# LandPatternBreakouts.net
KiCad netlist of a schematic drawn in EAGLE
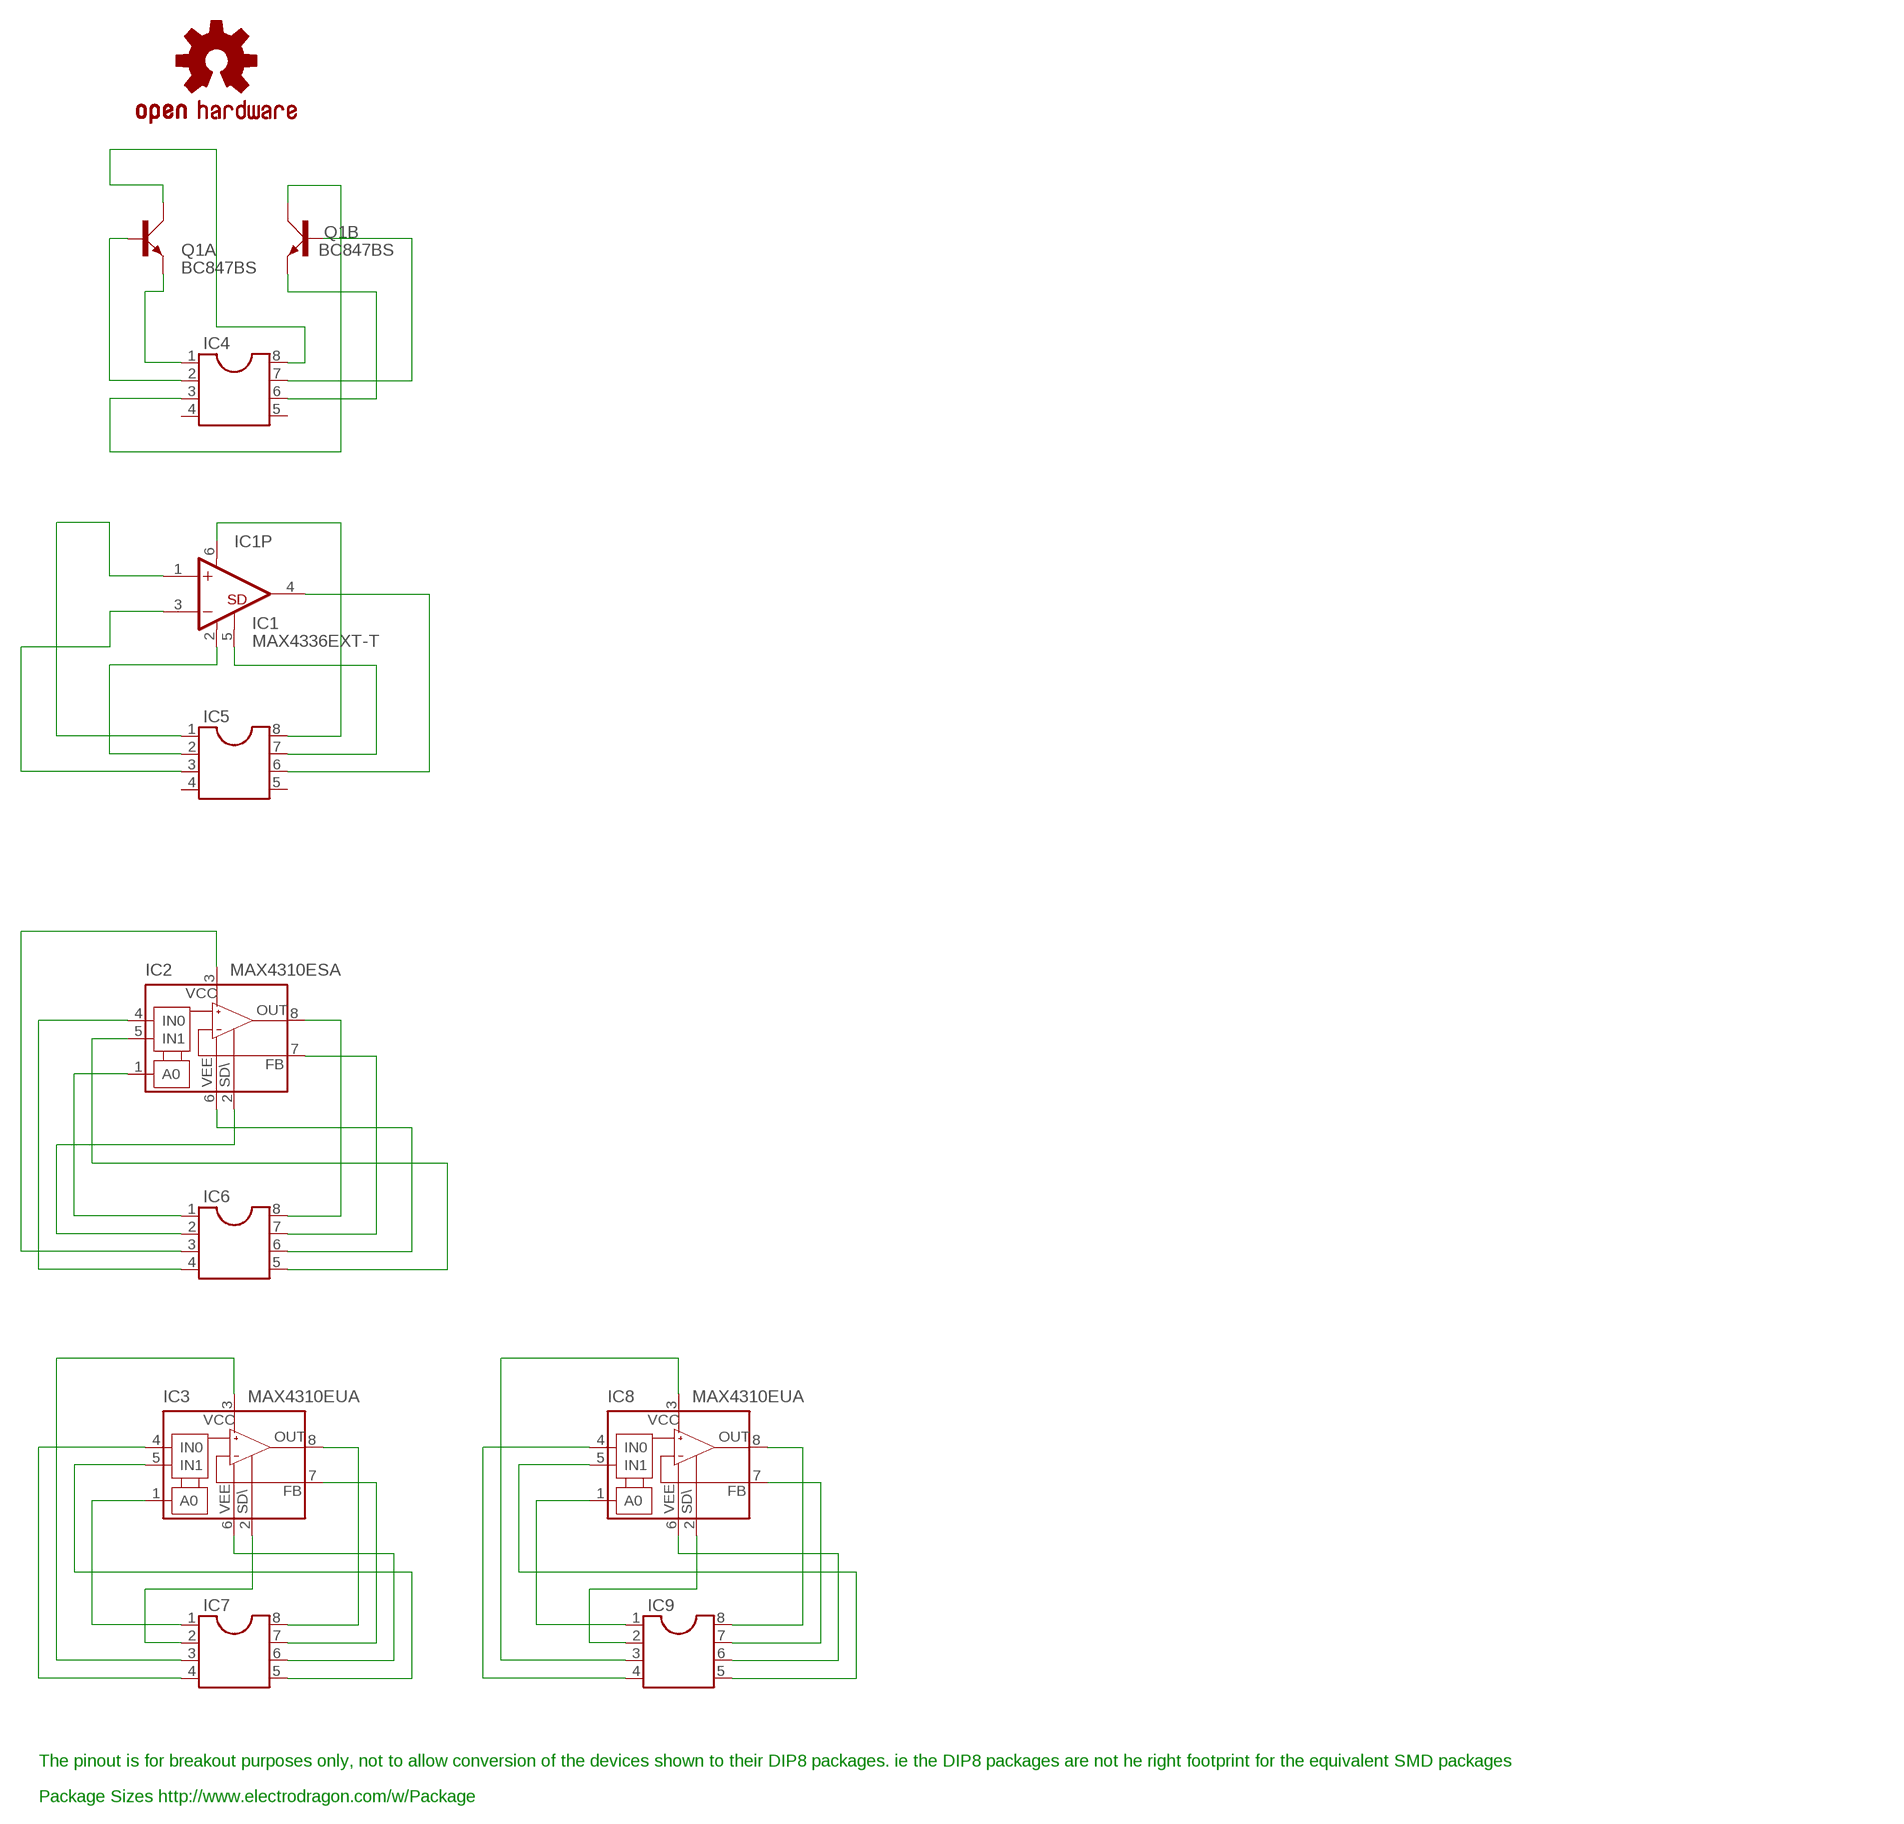
[diagram p0: schematic, sheet 1]

(export (version "E")
  (design (tool "Eeschema 10.0.6"))
  (components
    (comp (ref "IC1")
      (value "MAX4336EXT-T")
      (footprint "eagle-import:SOT23-6L")
      (fields (field (name "MPN") "MAX4336EXT+T"))
      (libsource (lib "eagle-import") (part "MAX4336EXT-T"))
    )
    (comp (ref "IC2")
      (value "MAX4310ESA")
      (footprint "eagle-import:UMAX8")
      (libsource (lib "eagle-import") (part "MAX4310ESA"))
    )
    (comp (ref "IC3")
      (value "MAX4310EUA")
      (footprint "eagle-import:SO08")
      (libsource (lib "eagle-import") (part "MAX4310EUA"))
    )
    (comp (ref "IC4")
      (value "DIL8")
      (footprint "eagle-import:DIL08")
      (libsource (lib "eagle-import") (part "DIL8"))
    )
    (comp (ref "IC5")
      (value "DIL8")
      (footprint "eagle-import:DIL08")
      (libsource (lib "eagle-import") (part "DIL8"))
    )
    (comp (ref "IC6")
      (value "DIL8")
      (footprint "eagle-import:DIL08")
      (libsource (lib "eagle-import") (part "DIL8"))
    )
    (comp (ref "IC7")
      (value "DIL8")
      (footprint "eagle-import:DIL08")
      (libsource (lib "eagle-import") (part "DIL8"))
    )
    (comp (ref "IC8")
      (value "MAX4310EUA")
      (footprint "eagle-import:SO08")
      (libsource (lib "eagle-import") (part "MAX4310EUA"))
    )
    (comp (ref "IC9")
      (value "DIL8")
      (footprint "eagle-import:DIL08")
      (libsource (lib "eagle-import") (part "DIL8"))
    )
    (comp (ref "LOGO1")
      (value "OSHW-LOGOS")
      (footprint "eagle-import:OSHW-LOGO-S")
      (libsource (lib "eagle-import") (part "OSHW-LOGOS"))
    )
    (comp (ref "Q1")
      (value "BC847BS")
      (footprint "eagle-import:SOT363_PHILIPS")
      (libsource (lib "eagle-import") (part "BC847BS"))
    )
  )
  (nets
    (net (code "1") (name "Net-(IC1A-+IN)") (class "Default")
      (node (ref "IC1") (pin "1") (pinfunction "+IN_1") (pintype "input"))
      (node (ref "IC5") (pin "1") (pinfunction "1_1") (pintype "passive"))
    )
    (net (code "2") (name "Net-(IC1A--IN)") (class "Default")
      (node (ref "IC1") (pin "3") (pinfunction "-IN_3") (pintype "input"))
      (node (ref "IC5") (pin "3") (pinfunction "3_3") (pintype "passive"))
    )
    (net (code "3") (name "Net-(IC1A-OUT)") (class "Default")
      (node (ref "IC1") (pin "4") (pinfunction "OUT_4") (pintype "output"))
      (node (ref "IC5") (pin "6") (pinfunction "6_6") (pintype "passive"))
    )
    (net (code "4") (name "Net-(IC1A-SHUTDOWN)") (class "Default")
      (node (ref "IC1") (pin "5") (pinfunction "SHUTDOWN_5") (pintype "passive"))
      (node (ref "IC5") (pin "7") (pinfunction "7_7") (pintype "passive"))
    )
    (net (code "5") (name "Net-(IC1B-V+)") (class "Default")
      (node (ref "IC1") (pin "6") (pinfunction "V+_6") (pintype "power_in"))
      (node (ref "IC5") (pin "8") (pinfunction "8_8") (pintype "passive"))
    )
    (net (code "6") (name "Net-(IC1B-V-)") (class "Default")
      (node (ref "IC1") (pin "2") (pinfunction "V-_2") (pintype "power_in"))
      (node (ref "IC5") (pin "2") (pinfunction "2_2") (pintype "passive"))
    )
    (net (code "7") (name "Net-(IC2-A0)") (class "Default")
      (node (ref "IC2") (pin "1") (pinfunction "A0_1") (pintype "input"))
      (node (ref "IC6") (pin "1") (pinfunction "1_1") (pintype "passive"))
    )
    (net (code "8") (name "Net-(IC2-FB)") (class "Default")
      (node (ref "IC2") (pin "7") (pinfunction "FB_7") (pintype "power_in"))
      (node (ref "IC6") (pin "7") (pinfunction "7_7") (pintype "passive"))
    )
    (net (code "9") (name "Net-(IC2-IN0)") (class "Default")
      (node (ref "IC2") (pin "4") (pinfunction "IN0_4") (pintype "input"))
      (node (ref "IC6") (pin "4") (pinfunction "4_4") (pintype "passive"))
    )
    (net (code "10") (name "Net-(IC2-IN1)") (class "Default")
      (node (ref "IC2") (pin "5") (pinfunction "IN1_5") (pintype "input"))
      (node (ref "IC6") (pin "5") (pinfunction "5_5") (pintype "passive"))
    )
    (net (code "11") (name "Net-(IC2-OUT)") (class "Default")
      (node (ref "IC2") (pin "8") (pinfunction "OUT_8") (pintype "output"))
      (node (ref "IC6") (pin "8") (pinfunction "8_8") (pintype "passive"))
    )
    (net (code "12") (name "Net-(IC2-V+)") (class "Default")
      (node (ref "IC2") (pin "3") (pinfunction "V+_3") (pintype "power_in"))
      (node (ref "IC6") (pin "3") (pinfunction "3_3") (pintype "passive"))
    )
    (net (code "13") (name "Net-(IC2-V-)") (class "Default")
      (node (ref "IC2") (pin "6") (pinfunction "V-_6") (pintype "power_in"))
      (node (ref "IC6") (pin "6") (pinfunction "6_6") (pintype "passive"))
    )
    (net (code "14") (name "Net-(IC2-~{SHDN})") (class "Default")
      (node (ref "IC2") (pin "2") (pinfunction "~{SHDN}_2") (pintype "input"))
      (node (ref "IC6") (pin "2") (pinfunction "2_2") (pintype "passive"))
    )
    (net (code "15") (name "Net-(IC3-A0)") (class "Default")
      (node (ref "IC3") (pin "1") (pinfunction "A0_1") (pintype "input"))
      (node (ref "IC7") (pin "1") (pinfunction "1_1") (pintype "passive"))
    )
    (net (code "16") (name "Net-(IC3-FB)") (class "Default")
      (node (ref "IC3") (pin "7") (pinfunction "FB_7") (pintype "power_in"))
      (node (ref "IC7") (pin "7") (pinfunction "7_7") (pintype "passive"))
    )
    (net (code "17") (name "Net-(IC3-IN0)") (class "Default")
      (node (ref "IC3") (pin "4") (pinfunction "IN0_4") (pintype "input"))
      (node (ref "IC7") (pin "4") (pinfunction "4_4") (pintype "passive"))
    )
    (net (code "18") (name "Net-(IC3-IN1)") (class "Default")
      (node (ref "IC3") (pin "5") (pinfunction "IN1_5") (pintype "input"))
      (node (ref "IC7") (pin "5") (pinfunction "5_5") (pintype "passive"))
    )
    (net (code "19") (name "Net-(IC3-OUT)") (class "Default")
      (node (ref "IC3") (pin "8") (pinfunction "OUT_8") (pintype "output"))
      (node (ref "IC7") (pin "8") (pinfunction "8_8") (pintype "passive"))
    )
    (net (code "20") (name "Net-(IC3-V+)") (class "Default")
      (node (ref "IC3") (pin "3") (pinfunction "V+_3") (pintype "power_in"))
      (node (ref "IC7") (pin "3") (pinfunction "3_3") (pintype "passive"))
    )
    (net (code "21") (name "Net-(IC3-V-)") (class "Default")
      (node (ref "IC3") (pin "6") (pinfunction "V-_6") (pintype "power_in"))
      (node (ref "IC7") (pin "6") (pinfunction "6_6") (pintype "passive"))
    )
    (net (code "22") (name "Net-(IC3-~{SHDN})") (class "Default")
      (node (ref "IC3") (pin "2") (pinfunction "~{SHDN}_2") (pintype "input"))
      (node (ref "IC7") (pin "2") (pinfunction "2_2") (pintype "passive"))
    )
    (net (code "23") (name "Net-(IC8-A0)") (class "Default")
      (node (ref "IC8") (pin "1") (pinfunction "A0_1") (pintype "input"))
      (node (ref "IC9") (pin "1") (pinfunction "1_1") (pintype "passive"))
    )
    (net (code "24") (name "Net-(IC8-FB)") (class "Default")
      (node (ref "IC8") (pin "7") (pinfunction "FB_7") (pintype "power_in"))
      (node (ref "IC9") (pin "7") (pinfunction "7_7") (pintype "passive"))
    )
    (net (code "25") (name "Net-(IC8-IN0)") (class "Default")
      (node (ref "IC8") (pin "4") (pinfunction "IN0_4") (pintype "input"))
      (node (ref "IC9") (pin "4") (pinfunction "4_4") (pintype "passive"))
    )
    (net (code "26") (name "Net-(IC8-IN1)") (class "Default")
      (node (ref "IC8") (pin "5") (pinfunction "IN1_5") (pintype "input"))
      (node (ref "IC9") (pin "5") (pinfunction "5_5") (pintype "passive"))
    )
    (net (code "27") (name "Net-(IC8-OUT)") (class "Default")
      (node (ref "IC8") (pin "8") (pinfunction "OUT_8") (pintype "output"))
      (node (ref "IC9") (pin "8") (pinfunction "8_8") (pintype "passive"))
    )
    (net (code "28") (name "Net-(IC8-V+)") (class "Default")
      (node (ref "IC8") (pin "3") (pinfunction "V+_3") (pintype "power_in"))
      (node (ref "IC9") (pin "3") (pinfunction "3_3") (pintype "passive"))
    )
    (net (code "29") (name "Net-(IC8-V-)") (class "Default")
      (node (ref "IC8") (pin "6") (pinfunction "V-_6") (pintype "power_in"))
      (node (ref "IC9") (pin "6") (pinfunction "6_6") (pintype "passive"))
    )
    (net (code "30") (name "Net-(IC8-~{SHDN})") (class "Default")
      (node (ref "IC8") (pin "2") (pinfunction "~{SHDN}_2") (pintype "input"))
      (node (ref "IC9") (pin "2") (pinfunction "2_2") (pintype "passive"))
    )
    (net (code "31") (name "Net-(Q1A-B)") (class "Default")
      (node (ref "IC4") (pin "2") (pinfunction "2_2") (pintype "passive"))
      (node (ref "Q1") (pin "2") (pinfunction "B_2") (pintype "passive"))
    )
    (net (code "32") (name "Net-(Q1A-C)") (class "Default")
      (node (ref "IC4") (pin "8") (pinfunction "8_8") (pintype "passive"))
      (node (ref "Q1") (pin "6") (pinfunction "C_6") (pintype "passive"))
    )
    (net (code "33") (name "Net-(Q1A-E)") (class "Default")
      (node (ref "IC4") (pin "1") (pinfunction "1_1") (pintype "passive"))
      (node (ref "Q1") (pin "1") (pinfunction "E_1") (pintype "passive"))
    )
    (net (code "34") (name "Net-(Q1B-B)") (class "Default")
      (node (ref "IC4") (pin "7") (pinfunction "7_7") (pintype "passive"))
      (node (ref "Q1") (pin "5") (pinfunction "B_5") (pintype "passive"))
    )
    (net (code "35") (name "Net-(Q1B-C)") (class "Default")
      (node (ref "IC4") (pin "3") (pinfunction "3_3") (pintype "passive"))
      (node (ref "Q1") (pin "3") (pinfunction "C_3") (pintype "passive"))
    )
    (net (code "36") (name "Net-(Q1B-E)") (class "Default")
      (node (ref "IC4") (pin "6") (pinfunction "6_6") (pintype "passive"))
      (node (ref "Q1") (pin "4") (pinfunction "E_4") (pintype "passive"))
    )
    (net (code "37") (name "unconnected-(IC4-Pad4)") (class "Default")
      (node (ref "IC4") (pin "4") (pinfunction "4_4") (pintype "passive"))
    )
    (net (code "38") (name "unconnected-(IC4-Pad5)") (class "Default")
      (node (ref "IC4") (pin "5") (pinfunction "5_5") (pintype "passive"))
    )
    (net (code "39") (name "unconnected-(IC5-Pad4)") (class "Default")
      (node (ref "IC5") (pin "4") (pinfunction "4_4") (pintype "passive"))
    )
    (net (code "40") (name "unconnected-(IC5-Pad5)") (class "Default")
      (node (ref "IC5") (pin "5") (pinfunction "5_5") (pintype "passive"))
    )
  )
)
